# 3v3_dcdc_blk.net
KiCad netlist of a schematic drawn in Altium Designer
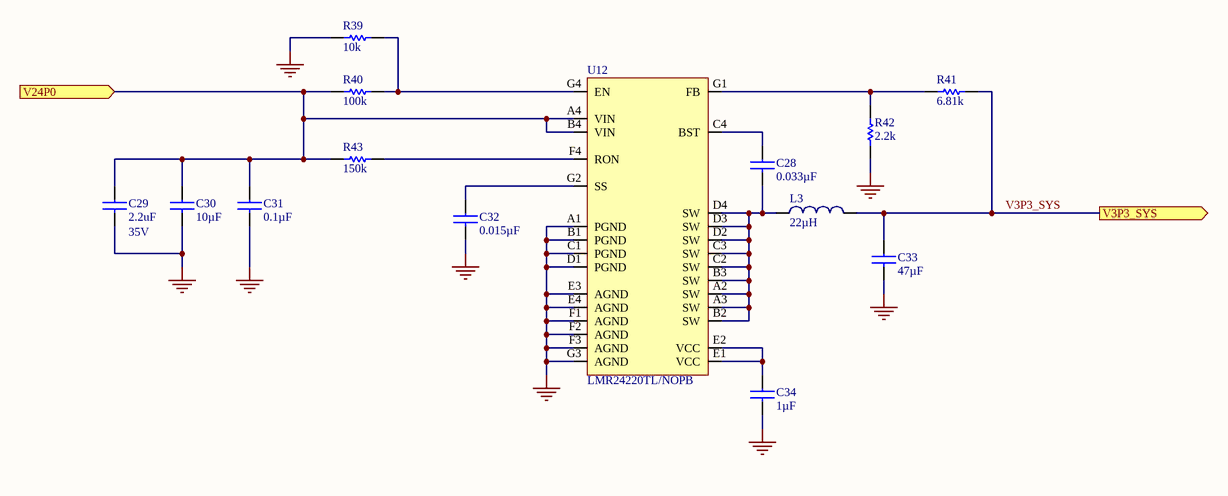
[diagram p0: 3v3_dcdc_blk.SchDoc]

(export (version "E")
  (design (tool "Eeschema 10.0.6"))
  (components
    (comp (ref "C28")
      (value "0.033µF")
      (footprint "C0402")
      (description "CAP CER 0.033UF 25V X7R 0402")
      (fields (field (name "MPN") "GRM155R71E333KA88D"))
      (libsource (lib "Capacitor") (part "GRM155R71E333KA88D"))
    )
    (comp (ref "C29")
      (value "2.2uF")
      (footprint "C0603")
      (description "CAP CER 2.2UF 35V X5R 0603")
      (fields (field (name "MPN") "C1608X5R1V225K080AC") (field (name "RATING") "35V"))
      (libsource (lib "Capacitor") (part "C1608X5R1V225K080AC"))
    )
    (comp (ref "C30")
      (value "10µF")
      (footprint "C1210")
      (description "CAP CER 10UF 35V X7R 1210")
      (fields (field (name "MPN") "GRM32ER7YA106KA12L"))
      (libsource (lib "Capacitor") (part "GRM32ER7YA106KA12L"))
    )
    (comp (ref "C31")
      (value "0.1µF")
      (footprint "C0805")
      (description "CAP CER 0.1UF 50V X7R 0805")
      (fields (field (name "MPN") "C0805C104K5RACTU"))
      (libsource (lib "Capacitor") (part "C0805C104K5RACTU"))
    )
    (comp (ref "C32")
      (value "0.015µF")
      (footprint "C0402")
      (description "CAP CER 0.015UF 25V X7R 0402")
      (fields (field (name "MPN") "GRM155R71E153KA61D"))
      (libsource (lib "Capacitor") (part "GRM155R71E153KA61D"))
    )
    (comp (ref "C33")
      (value "47µF")
      (footprint "C1206")
      (description "CAP CER 47UF 10V X5R 1206")
      (fields (field (name "MPN") "GRM31CR61A476KE15L"))
      (libsource (lib "Capacitor") (part "GRM31CR61A476KE15L"))
    )
    (comp (ref "C34")
      (value "1µF")
      (footprint "C0603")
      (description "CAP CER 1UF 25V X5R 0603")
      (fields (field (name "MPN") "GRM188R61E105KA12D"))
      (libsource (lib "Capacitor") (part "GRM188R61E105KA12D"))
    )
    (comp (ref "L3")
      (value "22µH")
      (footprint "MPI4040R3-220-R")
      (description "FIXED IND 22UH 1.1A 408 MOHM SMD")
      (fields (field (name "MPN") "MPI4040R3-220-R"))
      (libsource (lib "Inductor") (part "MPI4040R3-220-R"))
    )
    (comp (ref "R39")
      (value "10k")
      (footprint "R0402")
      (description "RES SMD 10K OHM 5% 1/16W 0402")
      (fields (field (name "MPN") "CRCW040210K0JNED"))
      (libsource (lib "Res") (part "CRCW040210K0JNED"))
    )
    (comp (ref "R40")
      (value "100k")
      (footprint "R0402")
      (description "RES SMD 100K OHM 1% 1/16W 0402")
      (fields (field (name "MPN") "CRCW0402100KFKED"))
      (libsource (lib "Res") (part "CRCW0402100KFKED"))
    )
    (comp (ref "R41")
      (value "6.81k")
      (footprint "R0402")
      (description "RES SMD 6.81KOHM 0.1% 1/16W 0402")
      (fields (field (name "MPN") "RT0402BRD076K81L"))
      (libsource (lib "Res") (part "RT0402BRD076K81L"))
    )
    (comp (ref "R42")
      (value "2.2k")
      (footprint "R0402")
      (description "RES SMD 2.2K OHM 1% 1/10W 0402")
      (fields (field (name "MPN") "ERJ-2RKF2201X"))
      (libsource (lib "Res") (part "ERJ-2RKF2201X"))
    )
    (comp (ref "R43")
      (value "150k")
      (footprint "R0402")
      (description "RES SMD 150K OHM 1% 1/16W 0402")
      (fields (field (name "MPN") "CRCW0402150KFKED"))
      (libsource (lib "Res") (part "CRCW0402150KFKED"))
    )
    (comp (ref "U12")
      (value "*")
      (footprint "DSBGA-28")
      (description "Voltage Regulators - Switching Regulators 42VIN,2A SIMPLE SW NANO STEP-DOWN REG")
      (fields (field (name "MPN") "LMR24220TL/NOPB"))
      (libsource (lib "IC") (part "LMR24220TL/NOPB"))
    )
  )
  (nets
    (net (code "1") (name "/V3P3_SYS") (class "Default")
      (node (ref "C33") (pin "1") (pinfunction "1_1") (pintype "passive"))
      (node (ref "L3") (pin "1") (pinfunction "1_1") (pintype "passive"))
      (node (ref "R41") (pin "2") (pinfunction "2_2") (pintype "passive"))
    )
    (net (code "2") (name "/V24P0") (class "Default")
      (node (ref "C29") (pin "1") (pinfunction "1_1") (pintype "passive"))
      (node (ref "C30") (pin "1") (pinfunction "1_1") (pintype "passive"))
      (node (ref "C31") (pin "1") (pinfunction "1_1") (pintype "passive"))
      (node (ref "R40") (pin "2") (pinfunction "2_2") (pintype "passive"))
      (node (ref "R43") (pin "2") (pinfunction "2_2") (pintype "passive"))
      (node (ref "U12") (pin "A4") (pinfunction "VIN_A4") (pintype "passive"))
      (node (ref "U12") (pin "B4") (pinfunction "VIN_B4") (pintype "passive"))
    )
    (net (code "3") (name "GND") (class "Default")
      (node (ref "C29") (pin "2") (pinfunction "2_2") (pintype "passive"))
      (node (ref "C30") (pin "2") (pinfunction "2_2") (pintype "passive"))
      (node (ref "C31") (pin "2") (pinfunction "2_2") (pintype "passive"))
      (node (ref "C32") (pin "2") (pinfunction "2_2") (pintype "passive"))
      (node (ref "C33") (pin "2") (pinfunction "2_2") (pintype "passive"))
      (node (ref "C34") (pin "2") (pinfunction "2_2") (pintype "passive"))
      (node (ref "R39") (pin "1") (pinfunction "1_1") (pintype "passive"))
      (node (ref "R42") (pin "1") (pinfunction "1_1") (pintype "passive"))
      (node (ref "U12") (pin "A1") (pinfunction "PGND_A1") (pintype "passive"))
      (node (ref "U12") (pin "B1") (pinfunction "PGND_B1") (pintype "passive"))
      (node (ref "U12") (pin "C1") (pinfunction "PGND_C1") (pintype "passive"))
      (node (ref "U12") (pin "D1") (pinfunction "PGND_D1") (pintype "passive"))
      (node (ref "U12") (pin "E3") (pinfunction "AGND_E3") (pintype "passive"))
      (node (ref "U12") (pin "E4") (pinfunction "AGND_E4") (pintype "passive"))
      (node (ref "U12") (pin "F1") (pinfunction "AGND_F1") (pintype "passive"))
      (node (ref "U12") (pin "F2") (pinfunction "AGND_F2") (pintype "passive"))
      (node (ref "U12") (pin "F3") (pinfunction "AGND_F3") (pintype "passive"))
      (node (ref "U12") (pin "G3") (pinfunction "AGND_G3") (pintype "passive"))
    )
    (net (code "4") (name "Net-(C28-Pad2)") (class "Default")
      (node (ref "C28") (pin "2") (pinfunction "2_2") (pintype "passive"))
      (node (ref "L3") (pin "2") (pinfunction "2_2") (pintype "passive"))
      (node (ref "U12") (pin "A2") (pinfunction "SW_A2") (pintype "passive"))
      (node (ref "U12") (pin "A3") (pinfunction "SW_A3") (pintype "passive"))
      (node (ref "U12") (pin "B2") (pinfunction "SW_B2") (pintype "passive"))
      (node (ref "U12") (pin "B3") (pinfunction "SW_B3") (pintype "passive"))
      (node (ref "U12") (pin "C2") (pinfunction "SW_C2") (pintype "passive"))
      (node (ref "U12") (pin "C3") (pinfunction "SW_C3") (pintype "passive"))
      (node (ref "U12") (pin "D2") (pinfunction "SW_D2") (pintype "passive"))
      (node (ref "U12") (pin "D3") (pinfunction "SW_D3") (pintype "passive"))
      (node (ref "U12") (pin "D4") (pinfunction "SW_D4") (pintype "passive"))
    )
    (net (code "5") (name "Net-(C34-Pad1)") (class "Default")
      (node (ref "C34") (pin "1") (pinfunction "1_1") (pintype "passive"))
      (node (ref "U12") (pin "E1") (pinfunction "VCC_E1") (pintype "passive"))
      (node (ref "U12") (pin "E2") (pinfunction "VCC_E2") (pintype "passive"))
    )
    (net (code "6") (name "Net-(U12-BST)") (class "Default")
      (node (ref "C28") (pin "1") (pinfunction "1_1") (pintype "passive"))
      (node (ref "U12") (pin "C4") (pinfunction "BST_C4") (pintype "passive"))
    )
    (net (code "7") (name "Net-(U12-EN)") (class "Default")
      (node (ref "R39") (pin "2") (pinfunction "2_2") (pintype "passive"))
      (node (ref "R40") (pin "1") (pinfunction "1_1") (pintype "passive"))
      (node (ref "U12") (pin "G4") (pinfunction "EN_G4") (pintype "passive"))
    )
    (net (code "8") (name "Net-(U12-FB)") (class "Default")
      (node (ref "R41") (pin "1") (pinfunction "1_1") (pintype "passive"))
      (node (ref "R42") (pin "2") (pinfunction "2_2") (pintype "passive"))
      (node (ref "U12") (pin "G1") (pinfunction "FB_G1") (pintype "passive"))
    )
    (net (code "9") (name "Net-(U12-RON)") (class "Default")
      (node (ref "R43") (pin "1") (pinfunction "1_1") (pintype "passive"))
      (node (ref "U12") (pin "F4") (pinfunction "RON_F4") (pintype "passive"))
    )
    (net (code "10") (name "Net-(U12-SS)") (class "Default")
      (node (ref "C32") (pin "1") (pinfunction "1_1") (pintype "passive"))
      (node (ref "U12") (pin "G2") (pinfunction "SS_G2") (pintype "passive"))
    )
  )
)
